# usb.net
KiCad netlist of a schematic drawn in Altium Designer
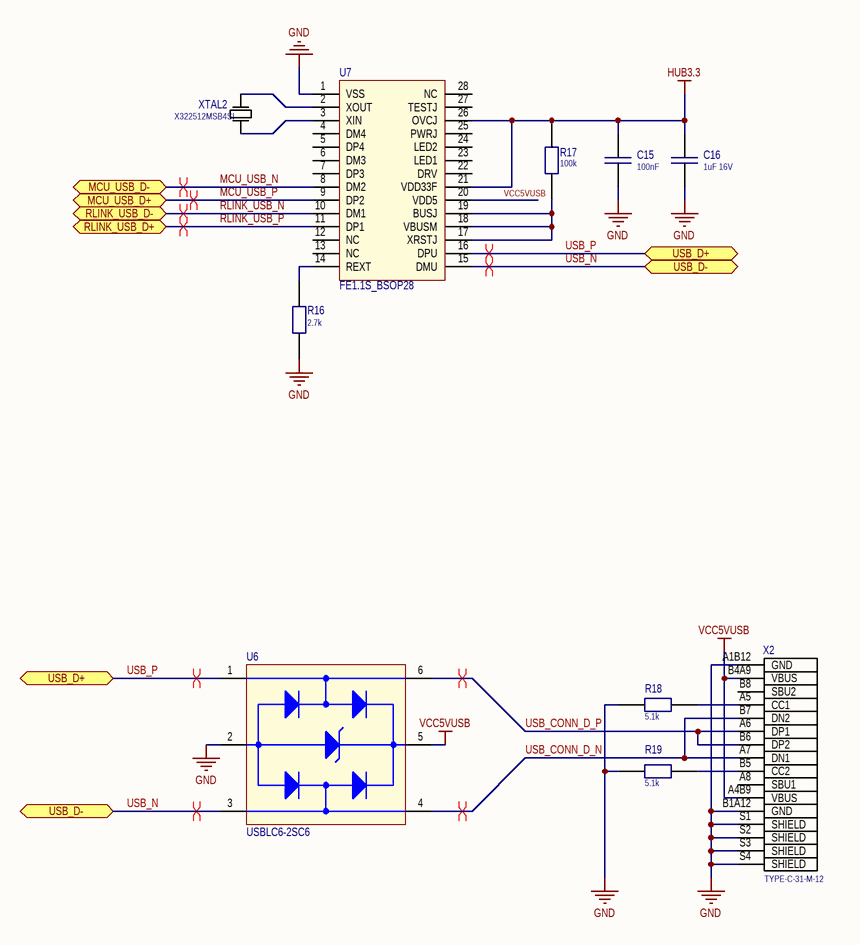
[diagram p0: usb.schdoc]

(export (version "E")
  (design (tool "Eeschema 10.0.6"))
  (components
    (comp (ref "C15")
      (value "100nF")
      (footprint "C_0603")
      (description "Capacitor")
      (fields (field (name "PART NUMBER") "CC0603JPX7R9BB104"))
      (libsource (lib "capacitors") (part "C0603"))
    )
    (comp (ref "C16")
      (value "1uF 16V")
      (footprint "C_0603")
      (description "Capacitor")
      (fields (field (name "PART NUMBER") "CC0603KRX7R7BB105"))
      (libsource (lib "capacitors") (part "C0603"))
    )
    (comp (ref "R16")
      (value "2.7k")
      (footprint "R_0603")
      (description "Resistor")
      (fields (field (name "PART NUMBER") "RC0603FR-072K7L"))
      (libsource (lib "resistors") (part "RES_SMD"))
    )
    (comp (ref "R17")
      (value "100k")
      (footprint "R_0603")
      (description "Resistor")
      (fields (field (name "PART NUMBER") "RC0603FR-07100KL"))
      (libsource (lib "resistors") (part "RES_SMD"))
    )
    (comp (ref "R18")
      (value "5.1k")
      (footprint "R_0603")
      (description "Resistor")
      (fields (field (name "PART NUMBER") "RC0603JR-075K1L"))
      (libsource (lib "resistors") (part "RES_SMD"))
    )
    (comp (ref "R19")
      (value "5.1k")
      (footprint "R_0603")
      (description "Resistor")
      (fields (field (name "PART NUMBER") "RC0603JR-075K1L"))
      (libsource (lib "resistors") (part "RES_SMD"))
    )
    (comp (ref "U6")
      (value "USBLC6-2SC6")
      (footprint "diode:SOT95P280X145-6N")
      (description "17V Clamp 5A (8/20Âµs) Ipp Tvs Diode Surface Mount SOT-23-6")
      (fields (field (name "MF") "STMicroelectronics"))
      (libsource (lib "diode") (part "USBLC6-2SC6"))
    )
    (comp (ref "U7")
      (value "FE1.1S_BSOP28")
      (footprint "BSOP28")
      (description "USB HUB 2.0")
      (fields (field (name "PART NUMBER") "FE1.1S-BSOP28BCN"))
      (libsource (lib "discret_ic") (part "FE1.1S_BSOP28"))
    )
    (comp (ref "X2")
      (value "TYPE-C-31-M-12")
      (footprint "connectors_socets:HRO_TYPE-C-31-M-12")
      (description "USB Connectors 24 Receptacle 1 8.94*7.3mm RoHS")
      (libsource (lib "connectors_socets") (part "TYPE-C-31-M-12"))
    )
    (comp (ref "XTAL2")
      (value "X322512MSB4SI")
      (footprint "NX3225GA")
      (description "Crystal Oscillator")
      (libsource (lib "bmplc") (part "NX3225GA"))
    )
  )
  (nets
    (net (code "1") (name "/MCU_USB_N") (class "Default")
      (node (ref "U7") (pin "8") (pinfunction "DM2_8") (pintype "passive"))
    )
    (net (code "2") (name "/MCU_USB_P") (class "Default")
      (node (ref "U7") (pin "9") (pinfunction "DP2_9") (pintype "passive"))
    )
    (net (code "3") (name "/RLINK_USB_N") (class "Default")
      (node (ref "U7") (pin "10") (pinfunction "DM1_10") (pintype "passive"))
    )
    (net (code "4") (name "/RLINK_USB_P") (class "Default")
      (node (ref "U7") (pin "11") (pinfunction "DP1_11") (pintype "passive"))
    )
    (net (code "5") (name "/USB_CONN_D_N") (class "Default")
      (node (ref "U6") (pin "4") (pinfunction "I/O2_OUT_4") (pintype "passive"))
      (node (ref "X2") (pin "A7") (pinfunction "DN1_A7") (pintype "passive"))
      (node (ref "X2") (pin "B7") (pinfunction "DN2_B7") (pintype "passive"))
    )
    (net (code "6") (name "/USB_CONN_D_P") (class "Default")
      (node (ref "U6") (pin "6") (pinfunction "I/O1_OUT_6") (pintype "passive"))
      (node (ref "X2") (pin "A6") (pinfunction "DP1_A6") (pintype "passive"))
      (node (ref "X2") (pin "B6") (pinfunction "DP2_B6") (pintype "passive"))
    )
    (net (code "7") (name "/USB_N") (class "Default")
      (node (ref "U6") (pin "3") (pinfunction "I/O2_IN_3") (pintype "passive"))
      (node (ref "U7") (pin "15") (pinfunction "DMU_15") (pintype "passive"))
    )
    (net (code "8") (name "/USB_P") (class "Default")
      (node (ref "U6") (pin "1") (pinfunction "I/O1_IN_1") (pintype "passive"))
      (node (ref "U7") (pin "16") (pinfunction "DPU_16") (pintype "passive"))
    )
    (net (code "9") (name "GND") (class "Default")
      (node (ref "C15") (pin "1") (pinfunction "1_1") (pintype "passive"))
      (node (ref "C16") (pin "1") (pinfunction "1_1") (pintype "passive"))
      (node (ref "R16") (pin "1") (pinfunction "1_1") (pintype "passive"))
      (node (ref "R18") (pin "1") (pinfunction "1_1") (pintype "passive"))
      (node (ref "R19") (pin "1") (pinfunction "1_1") (pintype "passive"))
      (node (ref "U6") (pin "2") (pinfunction "GND_2") (pintype "passive"))
      (node (ref "U7") (pin "1") (pinfunction "VSS_1") (pintype "passive"))
      (node (ref "X2") (pin "A1B12") (pinfunction "GND_A1B12") (pintype "passive"))
      (node (ref "X2") (pin "B1A12") (pinfunction "GND_B1A12") (pintype "passive"))
      (node (ref "X2") (pin "S1") (pinfunction "SHIELD_S1") (pintype "passive"))
      (node (ref "X2") (pin "S2") (pinfunction "SHIELD_S2") (pintype "passive"))
      (node (ref "X2") (pin "S3") (pinfunction "SHIELD_S3") (pintype "passive"))
      (node (ref "X2") (pin "S4") (pinfunction "SHIELD_S4") (pintype "passive"))
    )
    (net (code "10") (name "HUB3.3") (class "Default")
      (node (ref "C15") (pin "2") (pinfunction "2_2") (pintype "passive"))
      (node (ref "C16") (pin "2") (pinfunction "2_2") (pintype "passive"))
      (node (ref "R17") (pin "2") (pinfunction "2_2") (pintype "passive"))
      (node (ref "U7") (pin "21") (pinfunction "VDD33F_21") (pintype "passive"))
      (node (ref "U7") (pin "26") (pinfunction "OVCJ_26") (pintype "passive"))
    )
    (net (code "11") (name "Net-(U7-BUSJ)") (class "Default")
      (node (ref "R17") (pin "1") (pinfunction "1_1") (pintype "passive"))
      (node (ref "U7") (pin "17") (pinfunction "XRSTJ_17") (pintype "passive"))
      (node (ref "U7") (pin "18") (pinfunction "VBUSM_18") (pintype "passive"))
      (node (ref "U7") (pin "19") (pinfunction "BUSJ_19") (pintype "passive"))
    )
    (net (code "12") (name "Net-(U7-REXT)") (class "Default")
      (node (ref "R16") (pin "2") (pinfunction "2_2") (pintype "passive"))
      (node (ref "U7") (pin "14") (pinfunction "REXT_14") (pintype "passive"))
    )
    (net (code "13") (name "Net-(U7-XIN)") (class "Default")
      (node (ref "U7") (pin "3") (pinfunction "XIN_3") (pintype "passive"))
      (node (ref "XTAL2") (pin "3") (pinfunction "OSC2_3") (pintype "passive"))
    )
    (net (code "14") (name "Net-(U7-XOUT)") (class "Default")
      (node (ref "U7") (pin "2") (pinfunction "XOUT_2") (pintype "passive"))
      (node (ref "XTAL2") (pin "1") (pinfunction "OSC1_1") (pintype "passive"))
    )
    (net (code "15") (name "Net-(X2-CC1)") (class "Default")
      (node (ref "R18") (pin "2") (pinfunction "2_2") (pintype "passive"))
      (node (ref "X2") (pin "A5") (pinfunction "CC1_A5") (pintype "passive"))
    )
    (net (code "16") (name "Net-(X2-CC2)") (class "Default")
      (node (ref "R19") (pin "2") (pinfunction "2_2") (pintype "passive"))
      (node (ref "X2") (pin "B5") (pinfunction "CC2_B5") (pintype "passive"))
    )
    (net (code "17") (name "VCC5VUSB") (class "Default")
      (node (ref "U6") (pin "5") (pinfunction "VBUS_5") (pintype "passive"))
      (node (ref "U7") (pin "20") (pinfunction "VDD5_20") (pintype "passive"))
      (node (ref "X2") (pin "A4B9") (pinfunction "VBUS_A4B9") (pintype "passive"))
      (node (ref "X2") (pin "B4A9") (pinfunction "VBUS_B4A9") (pintype "passive"))
    )
    (net (code "18") (name "unconnected-(U7-DM3-Pad6)") (class "Default")
      (node (ref "U7") (pin "6") (pinfunction "DM3_6") (pintype "passive"))
    )
    (net (code "19") (name "unconnected-(U7-DM4-Pad4)") (class "Default")
      (node (ref "U7") (pin "4") (pinfunction "DM4_4") (pintype "passive"))
    )
    (net (code "20") (name "unconnected-(U7-DP3-Pad7)") (class "Default")
      (node (ref "U7") (pin "7") (pinfunction "DP3_7") (pintype "passive"))
    )
    (net (code "21") (name "unconnected-(U7-DP4-Pad5)") (class "Default")
      (node (ref "U7") (pin "5") (pinfunction "DP4_5") (pintype "passive"))
    )
    (net (code "22") (name "unconnected-(U7-DRV-Pad22)") (class "Default")
      (node (ref "U7") (pin "22") (pinfunction "DRV_22") (pintype "passive"))
    )
    (net (code "23") (name "unconnected-(U7-LED1-Pad23)") (class "Default")
      (node (ref "U7") (pin "23") (pinfunction "LED1_23") (pintype "passive"))
    )
    (net (code "24") (name "unconnected-(U7-LED2-Pad24)") (class "Default")
      (node (ref "U7") (pin "24") (pinfunction "LED2_24") (pintype "passive"))
    )
    (net (code "25") (name "unconnected-(U7-NC-Pad12)") (class "Default")
      (node (ref "U7") (pin "12") (pinfunction "NC_12") (pintype "passive"))
    )
    (net (code "26") (name "unconnected-(U7-NC-Pad13)") (class "Default")
      (node (ref "U7") (pin "13") (pinfunction "NC_13") (pintype "passive"))
    )
    (net (code "27") (name "unconnected-(U7-NC-Pad28)") (class "Default")
      (node (ref "U7") (pin "28") (pinfunction "NC_28") (pintype "passive"))
    )
    (net (code "28") (name "unconnected-(U7-PWRJ-Pad25)") (class "Default")
      (node (ref "U7") (pin "25") (pinfunction "PWRJ_25") (pintype "passive"))
    )
    (net (code "29") (name "unconnected-(U7-TESTJ-Pad27)") (class "Default")
      (node (ref "U7") (pin "27") (pinfunction "TESTJ_27") (pintype "passive"))
    )
    (net (code "30") (name "unconnected-(X2-SBU1-PadA8)") (class "Default")
      (node (ref "X2") (pin "A8") (pinfunction "SBU1_A8") (pintype "passive"))
    )
    (net (code "31") (name "unconnected-(X2-SBU2-PadB8)") (class "Default")
      (node (ref "X2") (pin "B8") (pinfunction "SBU2_B8") (pintype "passive"))
    )
  )
)
